# HeatPlatform.net
KiCad netlist of a schematic drawn in Altium Designer
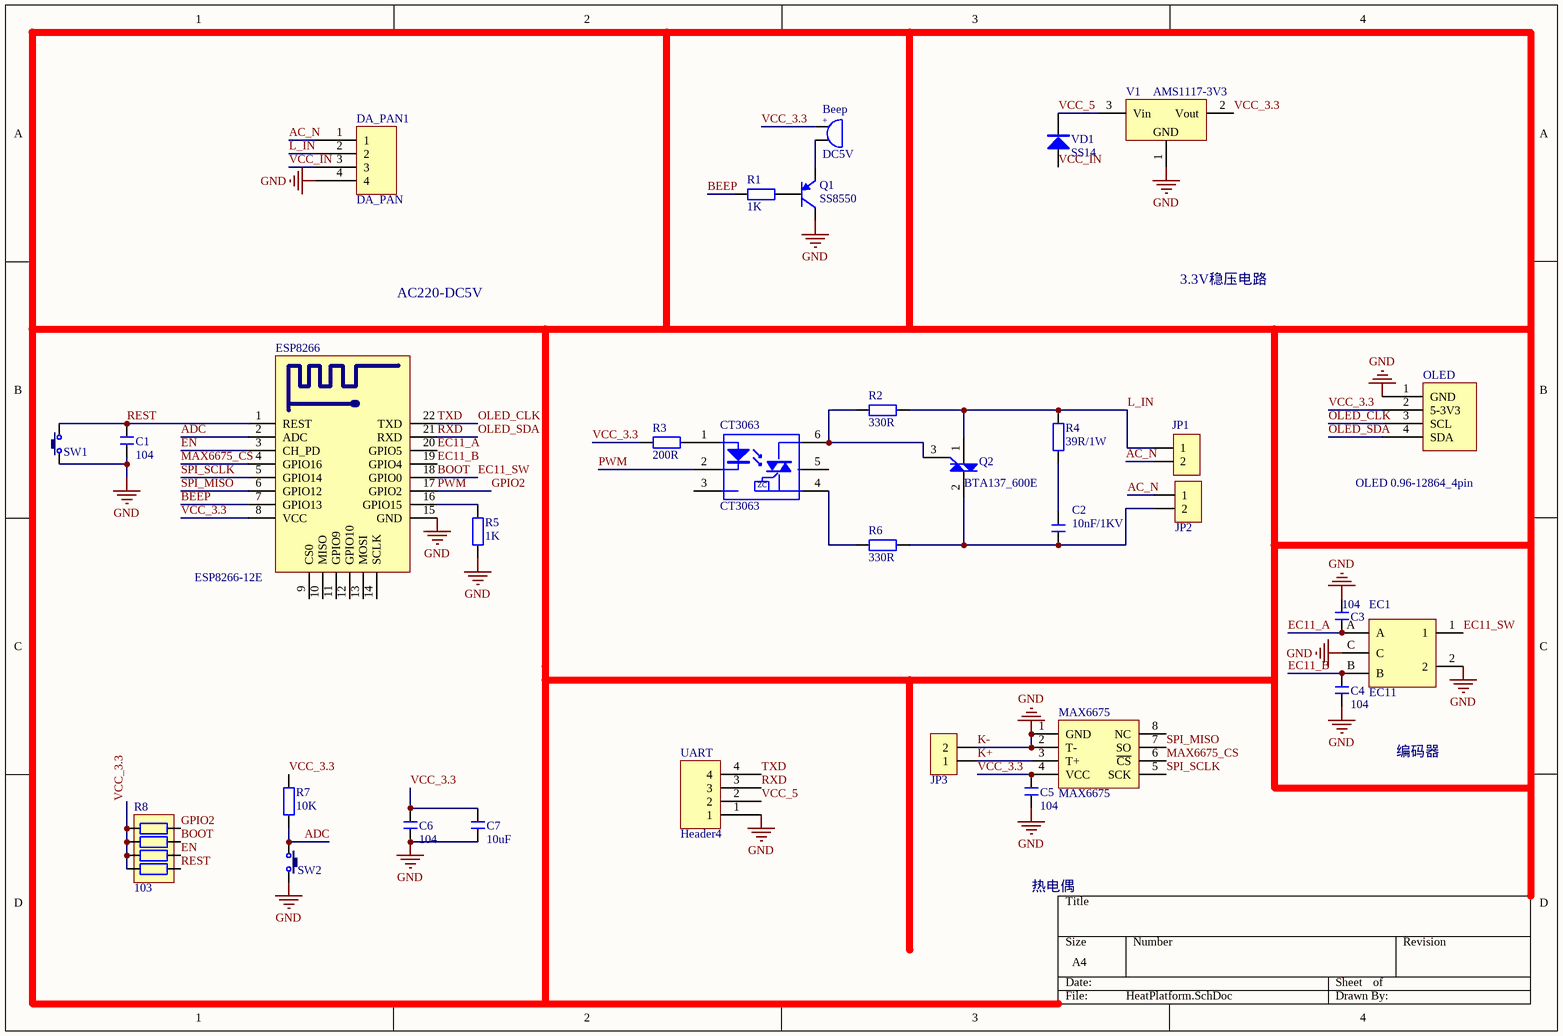
[diagram p0: HeatPlatform.SchDoc]

(export (version "E")
  (design (tool "Eeschema 10.0.6"))
  (components
    (comp (ref "Beep")
      (value "DC5V")
      (footprint "BEEP 5x9x5.5")
      (description "蜂鸣器")
      (fields (field (name "版权归属") "源创客"))
      (libsource (lib "HeatPlatform") (part "BEEP"))
    )
    (comp (ref "C1")
      (value "104")
      (footprint "C 0603")
      (description "无极性贴片电容")
      (fields (field (name "版权归属") "源创客"))
      (libsource (lib "HeatPlatform") (part "C"))
    )
    (comp (ref "C2")
      (value "10nF/1KV")
      (footprint "C 1210_L")
      (description "无极性贴片电容")
      (fields (field (name "版权归属") "源创客"))
      (libsource (lib "HeatPlatform") (part "C"))
    )
    (comp (ref "C3")
      (value "104")
      (footprint "C 0603")
      (description "无极性贴片电容")
      (fields (field (name "版权归属") "源创客"))
      (libsource (lib "HeatPlatform") (part "C"))
    )
    (comp (ref "C4")
      (value "104")
      (footprint "C 0603")
      (description "无极性贴片电容")
      (fields (field (name "版权归属") "源创客"))
      (libsource (lib "HeatPlatform") (part "C"))
    )
    (comp (ref "C5")
      (value "104")
      (footprint "C 0603")
      (description "无极性贴片电容")
      (fields (field (name "版权归属") "源创客"))
      (libsource (lib "HeatPlatform") (part "C"))
    )
    (comp (ref "C6")
      (value "104")
      (footprint "C 0603")
      (description "无极性贴片电容")
      (fields (field (name "版权归属") "源创客"))
      (libsource (lib "HeatPlatform") (part "C"))
    )
    (comp (ref "C7")
      (value "10uF")
      (footprint "C 0603")
      (description "无极性贴片电容")
      (fields (field (name "版权归属") "源创客"))
      (libsource (lib "HeatPlatform") (part "C"))
    )
    (comp (ref "CT3063")
      (value "CT3063")
      (footprint "SMD-6")
      (description "线性光耦（过零检测）")
      (fields (field (name "版权归属") "源创客"))
      (libsource (lib "HeatPlatform") (part "CT3063"))
    )
    (comp (ref "DA_PAN1")
      (value "DA_PAN")
      (footprint "DA_PAN")
      (libsource (lib "HeatPlatform") (part "DA_PAN"))
    )
    (comp (ref "EC1")
      (value "EC11")
      (footprint "EC11")
      (description "数字开关编码器")
      (fields (field (name "版权归属") "源创客"))
      (libsource (lib "HeatPlatform") (part "EC11"))
    )
    (comp (ref "ESP8266")
      (value "ESP8266-12E")
      (footprint "ESP_12E")
      (description "串口 WIFI模块，ESP-12E")
      (fields (field (name "版权归属") "源创客"))
      (libsource (lib "HeatPlatform") (part "ESP8266-12E"))
    )
    (comp (ref "JP1")
      (value "HDR-1X2")
      (footprint "HDR-1X2")
      (description "2P接插件")
      (fields (field (name "版权归属") "源创客"))
      (libsource (lib "HeatPlatform") (part "Header 2"))
    )
    (comp (ref "JP2")
      (value "HDR-1X2")
      (footprint "HDR-1X2")
      (description "2P接插件")
      (fields (field (name "版权归属") "源创客"))
      (libsource (lib "HeatPlatform") (part "Header 2"))
    )
    (comp (ref "JP3")
      (value "HDR-1X2")
      (footprint "HDR-1X2")
      (description "2P接插件")
      (fields (field (name "版权归属") "源创客"))
      (libsource (lib "") (part "Header 2_1"))
    )
    (comp (ref "MAX6675")
      (value "MAX6675")
      (footprint "SOP8_L")
      (description "K型热电偶检测芯片")
      (fields (field (name "版权归属") "源创客"))
      (libsource (lib "HeatPlatform") (part "MAX6675"))
    )
    (comp (ref "OLED")
      (value "OLED 0.96-12864_4pin")
      (footprint "OLED 0.96-12864_4pin")
      (description "12864 点阵屏")
      (libsource (lib "HeatPlatform") (part "OLED 0.96-12864_4pin"))
    )
    (comp (ref "Q1")
      (value "SS8550")
      (footprint "SOT23-3L")
      (description "高频放大-PNP型")
      (fields (field (name "版权归属") "源创客"))
      (libsource (lib "HeatPlatform") (part "8550-SMD"))
    )
    (comp (ref "Q2")
      (value "BTA137_600E")
      (footprint "TO252")
      (description "双向可控硅")
      (fields (field (name "版权归属") "源创客"))
      (libsource (lib "HeatPlatform") (part "BTA12_600"))
    )
    (comp (ref "R1")
      (value "1K")
      (footprint "R 0603")
      (description "贴片电阻")
      (fields (field (name "版权归属") "源创客"))
      (libsource (lib "HeatPlatform") (part "R"))
    )
    (comp (ref "R2")
      (value "330R")
      (footprint "R 0603")
      (description "贴片电阻")
      (fields (field (name "版权归属") "源创客"))
      (libsource (lib "HeatPlatform") (part "R"))
    )
    (comp (ref "R3")
      (value "200R")
      (footprint "R 0603")
      (description "贴片电阻")
      (fields (field (name "版权归属") "源创客"))
      (libsource (lib "HeatPlatform") (part "R"))
    )
    (comp (ref "R4")
      (value "39R/1W")
      (footprint "R 2512_L")
      (description "贴片电阻")
      (fields (field (name "版权归属") "源创客"))
      (libsource (lib "HeatPlatform") (part "R"))
    )
    (comp (ref "R5")
      (value "1K")
      (footprint "R 0603")
      (description "贴片电阻")
      (fields (field (name "版权归属") "源创客"))
      (libsource (lib "HeatPlatform") (part "R"))
    )
    (comp (ref "R6")
      (value "330R")
      (footprint "R 0603")
      (description "贴片电阻")
      (fields (field (name "版权归属") "源创客"))
      (libsource (lib "HeatPlatform") (part "R"))
    )
    (comp (ref "R7")
      (value "10K")
      (footprint "R 0603")
      (description "贴片电阻")
      (fields (field (name "版权归属") "源创客"))
      (libsource (lib "HeatPlatform") (part "R"))
    )
    (comp (ref "R8")
      (value "103")
      (footprint "RCA-8P4R-0603")
      (description "贴片网络排阻")
      (fields (field (name "版权归属") "源创客"))
      (libsource (lib "HeatPlatform") (part "R-8P4R"))
    )
    (comp (ref "SW1")
      (value "3*4*2")
      (footprint "TSW SMD-3*4*2")
      (description "3x4轻触开关")
      (fields (field (name "版权归属") "源创客"))
      (libsource (lib "HeatPlatform") (part "TSW 3x4"))
    )
    (comp (ref "SW2")
      (value "3*4*2")
      (footprint "TSW SMD-3*4*2")
      (description "3x4轻触开关")
      (fields (field (name "版权归属") "源创客"))
      (libsource (lib "") (part "TSW 3x4_1"))
    )
    (comp (ref "UART")
      (value "Header4")
      (footprint "HDR2.54-LI-4P")
      (libsource (lib "HeatPlatform") (part "Header4"))
    )
    (comp (ref "V1")
      (value "AMS1117-3V3")
      (footprint "SOT223_L")
      (description "三端稳压芯片")
      (fields (field (name "版权归属") "源创客"))
      (libsource (lib "HeatPlatform") (part "AMS1117"))
    )
    (comp (ref "VD1")
      (value "SS14")
      (footprint "SMA")
      (description "肖特基二极管")
      (fields (field (name "版权归属") "源创客"))
      (libsource (lib "HeatPlatform") (part "SS14"))
    )
  )
  (nets
    (net (code "1") (name "/AC_N") (class "Default")
      (node (ref "DA_PAN1") (pin "1") (pinfunction "1_1") (pintype "passive"))
      (node (ref "JP1") (pin "2") (pinfunction "2_2") (pintype "passive"))
      (node (ref "JP2") (pin "1") (pinfunction "1_1") (pintype "passive"))
    )
    (net (code "2") (name "/ADC") (class "Default")
      (node (ref "ESP8266") (pin "2") (pinfunction "ADC_2") (pintype "passive"))
      (node (ref "R7") (pin "1") (pinfunction "1_1") (pintype "passive"))
      (node (ref "SW2") (pin "1") (pinfunction "1_1") (pintype "passive"))
    )
    (net (code "3") (name "/BEEP") (class "Default")
      (node (ref "ESP8266") (pin "7") (pinfunction "GPIO13_7") (pintype "passive"))
      (node (ref "R1") (pin "1") (pinfunction "1_1") (pintype "passive"))
    )
    (net (code "4") (name "/BOOT") (class "Default")
      (node (ref "EC1") (pin "1") (pinfunction "1_1") (pintype "passive"))
      (node (ref "ESP8266") (pin "18") (pinfunction "GPIO0_18") (pintype "passive"))
      (node (ref "R8") (pin "7") (pinfunction "7_7") (pintype "passive"))
    )
    (net (code "5") (name "/EC11_A") (class "Default")
      (node (ref "C3") (pin "1") (pinfunction "1_1") (pintype "passive"))
      (node (ref "EC1") (pin "A") (pinfunction "A_A") (pintype "passive"))
      (node (ref "ESP8266") (pin "20") (pinfunction "GPIO5_20") (pintype "passive"))
    )
    (net (code "6") (name "/EC11_B") (class "Default")
      (node (ref "C4") (pin "2") (pinfunction "2_2") (pintype "passive"))
      (node (ref "EC1") (pin "B") (pinfunction "B_B") (pintype "passive"))
      (node (ref "ESP8266") (pin "19") (pinfunction "GPIO4_19") (pintype "passive"))
    )
    (net (code "7") (name "/EN") (class "Default")
      (node (ref "ESP8266") (pin "3") (pinfunction "CH_PD_3") (pintype "passive"))
      (node (ref "R8") (pin "6") (pinfunction "6_6") (pintype "passive"))
    )
    (net (code "8") (name "/GPIO2") (class "Default")
      (node (ref "CT3063") (pin "2") (pinfunction "C_2") (pintype "passive"))
      (node (ref "ESP8266") (pin "17") (pinfunction "GPIO2_17") (pintype "passive"))
      (node (ref "R8") (pin "8") (pinfunction "8_8") (pintype "passive"))
    )
    (net (code "9") (name "/K+") (class "Default")
      (node (ref "JP3") (pin "1") (pinfunction "1_1") (pintype "passive"))
      (node (ref "MAX6675") (pin "3") (pinfunction "T+_3") (pintype "passive"))
    )
    (net (code "10") (name "/L_IN") (class "Default")
      (node (ref "DA_PAN1") (pin "2") (pinfunction "2_2") (pintype "passive"))
      (node (ref "JP1") (pin "1") (pinfunction "1_1") (pintype "passive"))
      (node (ref "Q2") (pin "1") (pinfunction "A1_1") (pintype "passive"))
      (node (ref "R2") (pin "2") (pinfunction "2_2") (pintype "passive"))
      (node (ref "R4") (pin "2") (pinfunction "2_2") (pintype "passive"))
    )
    (net (code "11") (name "/MAX6675_CS") (class "Default")
      (node (ref "ESP8266") (pin "4") (pinfunction "GPIO16_4") (pintype "passive"))
      (node (ref "MAX6675") (pin "6") (pinfunction "~{CS}_6") (pintype "passive"))
    )
    (net (code "12") (name "/OLED_CLK") (class "Default")
      (node (ref "ESP8266") (pin "22") (pinfunction "TXD_22") (pintype "passive"))
      (node (ref "OLED") (pin "3") (pinfunction "SCL_3") (pintype "passive"))
      (node (ref "UART") (pin "4") (pinfunction "4_4") (pintype "passive"))
    )
    (net (code "13") (name "/OLED_SDA") (class "Default")
      (node (ref "ESP8266") (pin "21") (pinfunction "RXD_21") (pintype "passive"))
      (node (ref "OLED") (pin "4") (pinfunction "SDA_4") (pintype "passive"))
      (node (ref "UART") (pin "3") (pinfunction "3_3") (pintype "passive"))
    )
    (net (code "14") (name "/REST") (class "Default")
      (node (ref "C1") (pin "2") (pinfunction "2_2") (pintype "passive"))
      (node (ref "ESP8266") (pin "1") (pinfunction "REST_1") (pintype "passive"))
      (node (ref "R8") (pin "5") (pinfunction "5_5") (pintype "passive"))
      (node (ref "SW1") (pin "2") (pinfunction "2_2") (pintype "passive"))
    )
    (net (code "15") (name "/SPI_MISO") (class "Default")
      (node (ref "ESP8266") (pin "6") (pinfunction "GPIO12_6") (pintype "passive"))
      (node (ref "MAX6675") (pin "7") (pinfunction "SO_7") (pintype "passive"))
    )
    (net (code "16") (name "/SPI_SCLK") (class "Default")
      (node (ref "ESP8266") (pin "5") (pinfunction "GPIO14_5") (pintype "passive"))
      (node (ref "MAX6675") (pin "5") (pinfunction "SCK_5") (pintype "passive"))
    )
    (net (code "17") (name "/VCC_3.3") (class "Default")
      (node (ref "Beep") (pin "1") (pinfunction "1_1") (pintype "passive"))
      (node (ref "C5") (pin "2") (pinfunction "2_2") (pintype "passive"))
      (node (ref "C6") (pin "2") (pinfunction "2_2") (pintype "passive"))
      (node (ref "C7") (pin "2") (pinfunction "2_2") (pintype "passive"))
      (node (ref "ESP8266") (pin "8") (pinfunction "VCC_8") (pintype "passive"))
      (node (ref "MAX6675") (pin "4") (pinfunction "VCC_4") (pintype "passive"))
      (node (ref "OLED") (pin "2") (pinfunction "5-3V3_2") (pintype "passive"))
      (node (ref "R3") (pin "2") (pinfunction "2_2") (pintype "passive"))
      (node (ref "R7") (pin "2") (pinfunction "2_2") (pintype "passive"))
      (node (ref "R8") (pin "1") (pinfunction "1_1") (pintype "passive"))
      (node (ref "R8") (pin "2") (pinfunction "2_2") (pintype "passive"))
      (node (ref "R8") (pin "3") (pinfunction "3_3") (pintype "passive"))
      (node (ref "R8") (pin "4") (pinfunction "4_4") (pintype "passive"))
      (node (ref "V1") (pin "2") (pinfunction "Vout_2") (pintype "passive"))
    )
    (net (code "18") (name "/VCC_5") (class "Default")
      (node (ref "UART") (pin "2") (pinfunction "2_2") (pintype "passive"))
      (node (ref "V1") (pin "3") (pinfunction "Vin_3") (pintype "passive"))
      (node (ref "VD1") (pin "2") (pinfunction "K_2") (pintype "passive"))
    )
    (net (code "19") (name "/VCC_IN") (class "Default")
      (node (ref "DA_PAN1") (pin "3") (pinfunction "3_3") (pintype "passive"))
      (node (ref "VD1") (pin "1") (pinfunction "A_1") (pintype "passive"))
    )
    (net (code "20") (name "GND") (class "Default")
      (node (ref "C1") (pin "1") (pinfunction "1_1") (pintype "passive"))
      (node (ref "C3") (pin "2") (pinfunction "2_2") (pintype "passive"))
      (node (ref "C4") (pin "1") (pinfunction "1_1") (pintype "passive"))
      (node (ref "C5") (pin "1") (pinfunction "1_1") (pintype "passive"))
      (node (ref "C6") (pin "1") (pinfunction "1_1") (pintype "passive"))
      (node (ref "C7") (pin "1") (pinfunction "1_1") (pintype "passive"))
      (node (ref "DA_PAN1") (pin "4") (pinfunction "4_4") (pintype "passive"))
      (node (ref "EC1") (pin "2") (pinfunction "2_2") (pintype "passive"))
      (node (ref "EC1") (pin "C") (pinfunction "C_C") (pintype "passive"))
      (node (ref "ESP8266") (pin "15") (pinfunction "GND_15") (pintype "passive"))
      (node (ref "JP3") (pin "2") (pinfunction "2_2") (pintype "passive"))
      (node (ref "MAX6675") (pin "1") (pinfunction "GND_1") (pintype "passive"))
      (node (ref "MAX6675") (pin "2") (pinfunction "T-_2") (pintype "passive"))
      (node (ref "OLED") (pin "1") (pinfunction "GND_1") (pintype "passive"))
      (node (ref "Q1") (pin "3") (pinfunction "C_3") (pintype "passive"))
      (node (ref "R5") (pin "1") (pinfunction "1_1") (pintype "passive"))
      (node (ref "SW1") (pin "1") (pinfunction "1_1") (pintype "passive"))
      (node (ref "SW2") (pin "2") (pinfunction "2_2") (pintype "passive"))
      (node (ref "UART") (pin "1") (pinfunction "1_1") (pintype "passive"))
      (node (ref "V1") (pin "1") (pinfunction "GND_1") (pintype "passive"))
    )
    (net (code "21") (name "Net-(C2-Pad2)") (class "Default")
      (node (ref "C2") (pin "2") (pinfunction "2_2") (pintype "passive"))
      (node (ref "R4") (pin "1") (pinfunction "1_1") (pintype "passive"))
    )
    (net (code "22") (name "Net-(CT3063-A)") (class "Default")
      (node (ref "CT3063") (pin "1") (pinfunction "A_1") (pintype "passive"))
      (node (ref "R3") (pin "1") (pinfunction "1_1") (pintype "passive"))
    )
    (net (code "23") (name "Net-(CT3063-MT1)") (class "Default")
      (node (ref "CT3063") (pin "6") (pinfunction "MT1_6") (pintype "passive"))
      (node (ref "Q2") (pin "3") (pinfunction "G_3") (pintype "passive"))
      (node (ref "R2") (pin "1") (pinfunction "1_1") (pintype "passive"))
    )
    (net (code "24") (name "Net-(CT3063-MT2)") (class "Default")
      (node (ref "CT3063") (pin "4") (pinfunction "MT2_4") (pintype "passive"))
      (node (ref "R6") (pin "2") (pinfunction "2_2") (pintype "passive"))
    )
    (net (code "25") (name "Net-(ESP8266-GPIO15)") (class "Default")
      (node (ref "ESP8266") (pin "16") (pinfunction "GPIO15_16") (pintype "passive"))
      (node (ref "R5") (pin "2") (pinfunction "2_2") (pintype "passive"))
    )
    (net (code "26") (name "Net-(Q1-B)") (class "Default")
      (node (ref "Q1") (pin "1") (pinfunction "B_1") (pintype "passive"))
      (node (ref "R1") (pin "2") (pinfunction "2_2") (pintype "passive"))
    )
    (net (code "27") (name "Net-(Q1-E)") (class "Default")
      (node (ref "Beep") (pin "2") (pinfunction "2_2") (pintype "passive"))
      (node (ref "Q1") (pin "2") (pinfunction "E_2") (pintype "passive"))
    )
    (net (code "28") (name "Net-(Q2-A2)") (class "Default")
      (node (ref "C2") (pin "1") (pinfunction "1_1") (pintype "passive"))
      (node (ref "JP2") (pin "2") (pinfunction "2_2") (pintype "passive"))
      (node (ref "Q2") (pin "2") (pinfunction "A2_2") (pintype "passive"))
      (node (ref "R6") (pin "1") (pinfunction "1_1") (pintype "passive"))
    )
    (net (code "29") (name "unconnected-(CT3063-NC-Pad3)") (class "Default")
      (node (ref "CT3063") (pin "3") (pinfunction "NC_3") (pintype "passive"))
    )
    (net (code "30") (name "unconnected-(CT3063-NC-Pad5)") (class "Default")
      (node (ref "CT3063") (pin "5") (pinfunction "NC_5") (pintype "passive"))
    )
    (net (code "31") (name "unconnected-(ESP8266-CS0-Pad9)") (class "Default")
      (node (ref "ESP8266") (pin "9") (pinfunction "CS0_9") (pintype "passive"))
    )
    (net (code "32") (name "unconnected-(ESP8266-GPIO9-Pad11)") (class "Default")
      (node (ref "ESP8266") (pin "11") (pinfunction "GPIO9_11") (pintype "passive"))
    )
    (net (code "33") (name "unconnected-(ESP8266-GPIO10-Pad12)") (class "Default")
      (node (ref "ESP8266") (pin "12") (pinfunction "GPIO10_12") (pintype "passive"))
    )
    (net (code "34") (name "unconnected-(ESP8266-MISO-Pad10)") (class "Default")
      (node (ref "ESP8266") (pin "10") (pinfunction "MISO_10") (pintype "passive"))
    )
    (net (code "35") (name "unconnected-(ESP8266-MOSI-Pad13)") (class "Default")
      (node (ref "ESP8266") (pin "13") (pinfunction "MOSI_13") (pintype "passive"))
    )
    (net (code "36") (name "unconnected-(ESP8266-SCLK-Pad14)") (class "Default")
      (node (ref "ESP8266") (pin "14") (pinfunction "SCLK_14") (pintype "passive"))
    )
    (net (code "37") (name "unconnected-(MAX6675-NC-Pad8)") (class "Default")
      (node (ref "MAX6675") (pin "8") (pinfunction "NC_8") (pintype "passive"))
    )
  )
)
